# KSZ8851.net
KiCad netlist of a schematic drawn in EAGLE
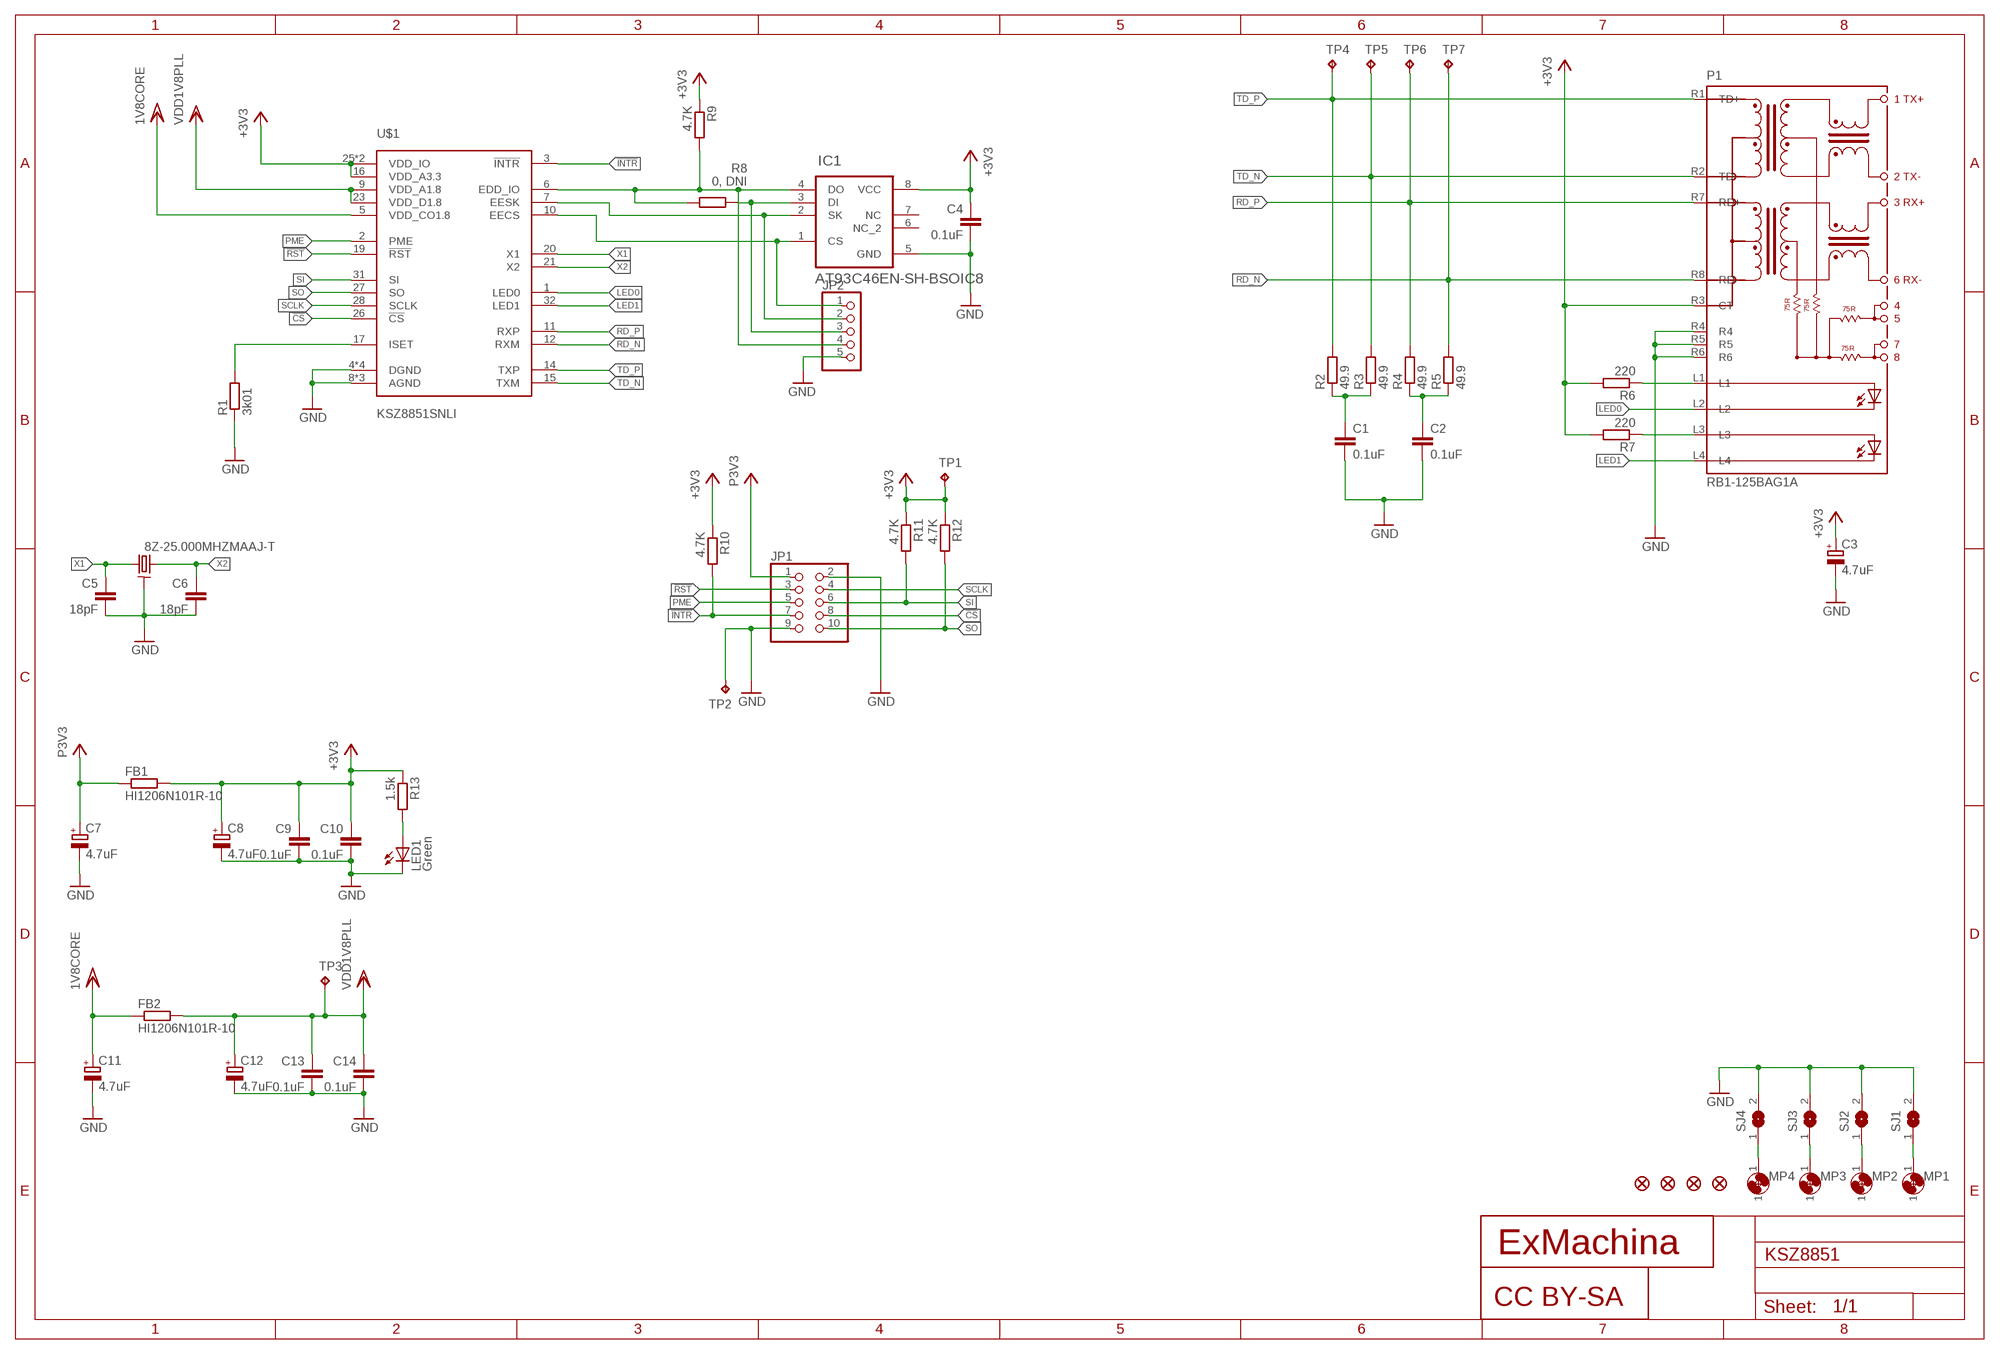
[diagram p0: schematic, sheet 1]

(export (version "E")
  (design (tool "Eeschema 10.0.6"))
  (components
    (comp (ref "-25.000MHZMAAJ-T1")
      (value "8Z-25.000MHZMAAJ-T")
      (footprint "eagle-import:SMD2.5X2")
      (fields (field (name "MPN") "8Z-25.000MAAJ-T"))
      (libsource (lib "eagle-import") (part "8Z-25.000MHZMAAJ-T"))
    )
    (comp (ref "C1")
      (value "0.1uF")
      (footprint "eagle-import:C0603")
      (fields (field (name "MPN") "MC0603B104K160CT"))
      (libsource (lib "eagle-import") (part "C-EUC0603"))
    )
    (comp (ref "C2")
      (value "0.1uF")
      (footprint "eagle-import:C0603")
      (fields (field (name "MPN") "MC0603B104K160CT"))
      (libsource (lib "eagle-import") (part "C-EUC0603"))
    )
    (comp (ref "C3")
      (value "4.7uF")
      (footprint "eagle-import:CT3216")
      (fields (field (name "MPN") "MCCTA475M010"))
      (libsource (lib "eagle-import") (part "CPOL-EUCT3216"))
    )
    (comp (ref "C4")
      (value "0.1uF")
      (footprint "eagle-import:C0603")
      (fields (field (name "MPN") "MC0603B104K160CT"))
      (libsource (lib "eagle-import") (part "C-EUC0603"))
    )
    (comp (ref "C5")
      (value "18pF")
      (footprint "eagle-import:C0603")
      (fields (field (name "MPN") "MC0603N180J500CT"))
      (libsource (lib "eagle-import") (part "C-EUC0603"))
    )
    (comp (ref "C6")
      (value "18pF")
      (footprint "eagle-import:C0603")
      (fields (field (name "MPN") "MC0603N180J500CT"))
      (libsource (lib "eagle-import") (part "C-EUC0603"))
    )
    (comp (ref "C7")
      (value "4.7uF")
      (footprint "eagle-import:CT3216")
      (fields (field (name "MPN") "MCCTA475M010"))
      (libsource (lib "eagle-import") (part "CPOL-EUCT3216"))
    )
    (comp (ref "C8")
      (value "4.7uF")
      (footprint "eagle-import:CT3216")
      (fields (field (name "MPN") "MCCTA475M010"))
      (libsource (lib "eagle-import") (part "CPOL-EUCT3216"))
    )
    (comp (ref "C9")
      (value "0.1uF")
      (footprint "eagle-import:C0603")
      (fields (field (name "MPN") "MC0603B104K160CT"))
      (libsource (lib "eagle-import") (part "C-EUC0603"))
    )
    (comp (ref "C10")
      (value "0.1uF")
      (footprint "eagle-import:C0603")
      (fields (field (name "MPN") "MC0603B104K160CT"))
      (libsource (lib "eagle-import") (part "C-EUC0603"))
    )
    (comp (ref "C11")
      (value "4.7uF")
      (footprint "eagle-import:CT3216")
      (fields (field (name "MPN") "MCCTA475M010"))
      (libsource (lib "eagle-import") (part "CPOL-EUCT3216"))
    )
    (comp (ref "C12")
      (value "4.7uF")
      (footprint "eagle-import:CT3216")
      (fields (field (name "MPN") "MCCTA475M010"))
      (libsource (lib "eagle-import") (part "CPOL-EUCT3216"))
    )
    (comp (ref "C13")
      (value "0.1uF")
      (footprint "eagle-import:C0603")
      (fields (field (name "MPN") "MC0603B104K160CT"))
      (libsource (lib "eagle-import") (part "C-EUC0603"))
    )
    (comp (ref "C14")
      (value "0.1uF")
      (footprint "eagle-import:C0603")
      (fields (field (name "MPN") "MC0603B104K160CT"))
      (libsource (lib "eagle-import") (part "C-EUC0603"))
    )
    (comp (ref "FB1")
      (value "HI1206N101R-10")
      (footprint "eagle-import:1206")
      (libsource (lib "eagle-import") (part "HI?N101R-101206"))
    )
    (comp (ref "FB2")
      (value "HI1206N101R-10")
      (footprint "eagle-import:1206")
      (libsource (lib "eagle-import") (part "HI?N101R-101206"))
    )
    (comp (ref "IC1")
      (value "AT93C46EN-SH-BSOIC8")
      (footprint "eagle-import:SOIC8")
      (fields (field (name "MPN") "AT93C46EN-SH-T"))
      (libsource (lib "eagle-import") (part "AT93C46EN-SH-BSOIC8"))
    )
    (comp (ref "JP1")
      (value "PINHD-2X5")
      (footprint "eagle-import:2X05")
      (fields (field (name "MPN") "M20-9980546"))
      (libsource (lib "eagle-import") (part "PINHD-2X5"))
    )
    (comp (ref "JP2")
      (value "PINHD-1X55X2MM")
      (footprint "eagle-import:1_05X2MM")
      (fields (field (name "MF") "FARNELL") (field (name "MPN") "M22-2010505"))
      (libsource (lib "eagle-import") (part "PINHD-1X55X2MM"))
    )
    (comp (ref "JP3")
      (value "FIDUCIAL1X2")
      (footprint "eagle-import:FIDUCIAL-1X2")
      (libsource (lib "eagle-import") (part "FIDUCIAL1X2"))
    )
    (comp (ref "JP4")
      (value "FIDUCIAL1X2")
      (footprint "eagle-import:FIDUCIAL-1X2")
      (libsource (lib "eagle-import") (part "FIDUCIAL1X2"))
    )
    (comp (ref "JP5")
      (value "FIDUCIAL1X2")
      (footprint "eagle-import:FIDUCIAL-1X2")
      (libsource (lib "eagle-import") (part "FIDUCIAL1X2"))
    )
    (comp (ref "JP6")
      (value "FIDUCIAL1X2")
      (footprint "eagle-import:FIDUCIAL-1X2")
      (libsource (lib "eagle-import") (part "FIDUCIAL1X2"))
    )
    (comp (ref "LED1")
      (value "Green")
      (footprint "eagle-import:SML0603")
      (fields (field (name "MPN") "OVS-0604"))
      (libsource (lib "eagle-import") (part "LEDSML0603"))
    )
    (comp (ref "MP1")
      (value "MOUNT-PAD2.5")
      (footprint "eagle-import:P2.5")
      (libsource (lib "eagle-import") (part "MOUNT-PAD2.5"))
    )
    (comp (ref "MP2")
      (value "MOUNT-PAD2.5")
      (footprint "eagle-import:P2.5")
      (libsource (lib "eagle-import") (part "MOUNT-PAD2.5"))
    )
    (comp (ref "MP3")
      (value "MOUNT-PAD2.5")
      (footprint "eagle-import:P2.5")
      (libsource (lib "eagle-import") (part "MOUNT-PAD2.5"))
    )
    (comp (ref "MP4")
      (value "MOUNT-PAD2.5")
      (footprint "eagle-import:P2.5")
      (libsource (lib "eagle-import") (part "MOUNT-PAD2.5"))
    )
    (comp (ref "P1")
      (value "RB1-125BAG1A")
      (footprint "eagle-import:WIZNET_RB1-125BAG1A")
      (libsource (lib "eagle-import") (part "RB1-125BAG1A"))
    )
    (comp (ref "R1")
      (value "3k01")
      (footprint "eagle-import:R0603")
      (fields (field (name "MPN") "MC0063W060313K01"))
      (libsource (lib "eagle-import") (part "R-EU_R0603"))
    )
    (comp (ref "R2")
      (value "49.9")
      (footprint "eagle-import:R0603")
      (fields (field (name "MPN") "MC0603SAF499JT5E"))
      (libsource (lib "eagle-import") (part "R-EU_R0603"))
    )
    (comp (ref "R3")
      (value "49.9")
      (footprint "eagle-import:R0603")
      (fields (field (name "MPN") "MC0603SAF499JT5E"))
      (libsource (lib "eagle-import") (part "R-EU_R0603"))
    )
    (comp (ref "R4")
      (value "49.9")
      (footprint "eagle-import:R0603")
      (fields (field (name "MPN") "MC0603SAF499JT5E"))
      (libsource (lib "eagle-import") (part "R-EU_R0603"))
    )
    (comp (ref "R5")
      (value "49.9")
      (footprint "eagle-import:R0603")
      (fields (field (name "MPN") "MC0603SAF499JT5E"))
      (libsource (lib "eagle-import") (part "R-EU_R0603"))
    )
    (comp (ref "R6")
      (value "220")
      (footprint "eagle-import:R0603")
      (fields (field (name "MF") "Multicomp Passives") (field (name "MPN") "MC0063W06031220R"))
      (libsource (lib "eagle-import") (part "R-EU_R0603"))
    )
    (comp (ref "R7")
      (value "220")
      (footprint "eagle-import:R0603")
      (fields (field (name "MF") "Multicomp Passives") (field (name "MPN") "MC0063W06031220R"))
      (libsource (lib "eagle-import") (part "R-EU_R0603"))
    )
    (comp (ref "R8")
      (value "0, DNI")
      (footprint "eagle-import:R0603")
      (fields (field (name "MF") "Multicomp Passives") (field (name "MPN") "MC0603WG00000T5E-TC"))
      (libsource (lib "eagle-import") (part "R-EU_R0603"))
    )
    (comp (ref "R9")
      (value "4.7K")
      (footprint "eagle-import:R0603")
      (fields (field (name "MF") "Multicomp Passives") (field (name "MPN") "MC0063W060314K7"))
      (libsource (lib "eagle-import") (part "R-EU_R0603"))
    )
    (comp (ref "R10")
      (value "4.7K")
      (footprint "eagle-import:R0603")
      (fields (field (name "MF") "Multicomp Passives") (field (name "MPN") "MC0063W060314K7"))
      (libsource (lib "eagle-import") (part "R-EU_R0603"))
    )
    (comp (ref "R11")
      (value "4.7K")
      (footprint "eagle-import:R0603")
      (fields (field (name "MF") "Multicomp Passives") (field (name "MPN") "MC0063W060314K7"))
      (libsource (lib "eagle-import") (part "R-EU_R0603"))
    )
    (comp (ref "R12")
      (value "4.7K")
      (footprint "eagle-import:R0603")
      (fields (field (name "MF") "Multicomp Passives") (field (name "MPN") "MC0063W060314K7"))
      (libsource (lib "eagle-import") (part "R-EU_R0603"))
    )
    (comp (ref "R13")
      (value "1.5k")
      (footprint "eagle-import:R0603")
      (fields (field (name "MPN") "MCMR06X1501FTL"))
      (libsource (lib "eagle-import") (part "R-EU_R0603"))
    )
    (comp (ref "SJ1") (value "SJ") (footprint "eagle-import:SJ") (libsource (lib "eagle-import") (part "SJ")))
    (comp (ref "SJ2") (value "SJ") (footprint "eagle-import:SJ") (libsource (lib "eagle-import") (part "SJ")))
    (comp (ref "SJ3") (value "SJ") (footprint "eagle-import:SJ") (libsource (lib "eagle-import") (part "SJ")))
    (comp (ref "SJ4") (value "SJ") (footprint "eagle-import:SJ") (libsource (lib "eagle-import") (part "SJ")))
    (comp (ref "TP1")
      (value "TPB2,54")
      (footprint "eagle-import:B2,54")
      (libsource (lib "eagle-import") (part "TPB2,54"))
    )
    (comp (ref "TP2")
      (value "TPB2,54")
      (footprint "eagle-import:B2,54")
      (libsource (lib "eagle-import") (part "TPB2,54"))
    )
    (comp (ref "TP3")
      (value "TPB2,54")
      (footprint "eagle-import:B2,54")
      (libsource (lib "eagle-import") (part "TPB2,54"))
    )
    (comp (ref "TP4")
      (value "TPB1,27")
      (footprint "eagle-import:B1,27")
      (libsource (lib "eagle-import") (part "TPB1,27"))
    )
    (comp (ref "TP5")
      (value "TPB1,27")
      (footprint "eagle-import:B1,27")
      (libsource (lib "eagle-import") (part "TPB1,27"))
    )
    (comp (ref "TP6")
      (value "TPB1,27")
      (footprint "eagle-import:B1,27")
      (libsource (lib "eagle-import") (part "TPB1,27"))
    )
    (comp (ref "TP7")
      (value "TPB1,27")
      (footprint "eagle-import:B1,27")
      (libsource (lib "eagle-import") (part "TPB1,27"))
    )
    (comp (ref "U$1")
      (value "KSZ8851SNLI")
      (footprint "eagle-import:QFN50P500X500X85-32L")
      (fields (field (name "MPN") "KSZ8851SNLI-TR"))
      (libsource (lib "eagle-import") (part "KSZ8851SNLI"))
    )
    (comp (ref "U$2")
      (value "EXMACHINA-LOGO-NAME")
      (footprint "eagle-import:EXM-LOGO-BASELINE")
      (libsource (lib "eagle-import") (part "EXMACHINA-LOGO-NAME"))
    )
    (comp (ref "U$3")
      (value "CC-BY-SA")
      (footprint "eagle-import:CC-BY-SA")
      (libsource (lib "eagle-import") (part "CC-BY-SA"))
    )
  )
  (nets
    (net (code "1") (name "+3V3") (class "Default")
      (node (ref "C10") (pin "1") (pinfunction "1_1") (pintype "passive"))
      (node (ref "C3") (pin "+") (pinfunction "+_+") (pintype "passive"))
      (node (ref "C4") (pin "1") (pinfunction "1_1") (pintype "passive"))
      (node (ref "C8") (pin "+") (pinfunction "+_+") (pintype "passive"))
      (node (ref "C9") (pin "1") (pinfunction "1_1") (pintype "passive"))
      (node (ref "FB1") (pin "2") (pinfunction "2_2") (pintype "passive"))
      (node (ref "IC1") (pin "8") (pinfunction "VCC_8") (pintype "power_in"))
      (node (ref "P1") (pin "R3") (pinfunction "CT_R3") (pintype "input"))
      (node (ref "R10") (pin "1") (pinfunction "1_1") (pintype "passive"))
      (node (ref "R11") (pin "1") (pinfunction "1_1") (pintype "passive"))
      (node (ref "R12") (pin "1") (pinfunction "1_1") (pintype "passive"))
      (node (ref "R13") (pin "1") (pinfunction "1_1") (pintype "passive"))
      (node (ref "R6") (pin "2") (pinfunction "2_2") (pintype "passive"))
      (node (ref "R7") (pin "2") (pinfunction "2_2") (pintype "passive"))
      (node (ref "R9") (pin "1") (pinfunction "1_1") (pintype "passive"))
      (node (ref "TP1") (pin "TP") (pinfunction "TP_TP") (pintype "input"))
      (node (ref "U$1") (pin "16") (pinfunction "VDD_A3.3_16") (pintype "power_in"))
      (node (ref "U$1") (pin "25") (pinfunction "VDD_IO_25") (pintype "power_in"))
      (node (ref "U$1") (pin "30") (pinfunction "VDD_IO_30") (pintype "power_in"))
    )
    (net (code "2") (name "/~{CS}") (class "Default")
      (node (ref "JP1") (pin "8") (pinfunction "8_8") (pintype "passive"))
      (node (ref "U$1") (pin "26") (pinfunction "~{CS}_26") (pintype "input"))
    )
    (net (code "3") (name "/~{INTR}") (class "Default")
      (node (ref "JP1") (pin "7") (pinfunction "7_7") (pintype "passive"))
      (node (ref "R10") (pin "2") (pinfunction "2_2") (pintype "passive"))
      (node (ref "U$1") (pin "3") (pinfunction "~{INTR}_3") (pintype "output"))
    )
    (net (code "4") (name "/~{RST}") (class "Default")
      (node (ref "JP1") (pin "3") (pinfunction "3_3") (pintype "passive"))
      (node (ref "U$1") (pin "19") (pinfunction "~{RST}_19") (pintype "input"))
    )
    (net (code "5") (name "1V8CORE") (class "Default")
      (node (ref "C11") (pin "+") (pinfunction "+_+") (pintype "passive"))
      (node (ref "FB2") (pin "1") (pinfunction "1_1") (pintype "passive"))
      (node (ref "U$1") (pin "5") (pinfunction "VDD_CO1.8_5") (pintype "power_in"))
    )
    (net (code "6") (name "GND") (class "Default")
      (node (ref "-25.000MHZMAAJ-T1") (pin "2") (pinfunction "2_2") (pintype "passive"))
      (node (ref "-25.000MHZMAAJ-T1") (pin "4") (pinfunction "2_4") (pintype "passive"))
      (node (ref "C1") (pin "2") (pinfunction "2_2") (pintype "passive"))
      (node (ref "C10") (pin "2") (pinfunction "2_2") (pintype "passive"))
      (node (ref "C11") (pin "-") (pinfunction "-_-") (pintype "passive"))
      (node (ref "C12") (pin "-") (pinfunction "-_-") (pintype "passive"))
      (node (ref "C13") (pin "2") (pinfunction "2_2") (pintype "passive"))
      (node (ref "C14") (pin "2") (pinfunction "2_2") (pintype "passive"))
      (node (ref "C2") (pin "2") (pinfunction "2_2") (pintype "passive"))
      (node (ref "C3") (pin "-") (pinfunction "-_-") (pintype "passive"))
      (node (ref "C4") (pin "2") (pinfunction "2_2") (pintype "passive"))
      (node (ref "C5") (pin "2") (pinfunction "2_2") (pintype "passive"))
      (node (ref "C6") (pin "2") (pinfunction "2_2") (pintype "passive"))
      (node (ref "C7") (pin "-") (pinfunction "-_-") (pintype "passive"))
      (node (ref "C8") (pin "-") (pinfunction "-_-") (pintype "passive"))
      (node (ref "C9") (pin "2") (pinfunction "2_2") (pintype "passive"))
      (node (ref "IC1") (pin "5") (pinfunction "GND_5") (pintype "passive"))
      (node (ref "JP1") (pin "2") (pinfunction "2_2") (pintype "passive"))
      (node (ref "JP1") (pin "9") (pinfunction "9_9") (pintype "passive"))
      (node (ref "JP2") (pin "5") (pinfunction "5_5") (pintype "passive"))
      (node (ref "LED1") (pin "C") (pinfunction "C_C") (pintype "passive"))
      (node (ref "P1") (pin "R4") (pinfunction "R4_R4") (pintype "input"))
      (node (ref "P1") (pin "R5") (pinfunction "R5_R5") (pintype "input"))
      (node (ref "P1") (pin "R6") (pinfunction "R6_R6") (pintype "input"))
      (node (ref "R1") (pin "1") (pinfunction "1_1") (pintype "passive"))
      (node (ref "SJ1") (pin "2") (pinfunction "2_2") (pintype "passive"))
      (node (ref "SJ2") (pin "2") (pinfunction "2_2") (pintype "passive"))
      (node (ref "SJ3") (pin "2") (pinfunction "2_2") (pintype "passive"))
      (node (ref "SJ4") (pin "2") (pinfunction "2_2") (pintype "passive"))
      (node (ref "TP2") (pin "TP") (pinfunction "TP_TP") (pintype "input"))
      (node (ref "U$1") (pin "13") (pinfunction "AGND_13") (pintype "power_in"))
      (node (ref "U$1") (pin "18") (pinfunction "AGND_18") (pintype "power_in"))
      (node (ref "U$1") (pin "22") (pinfunction "DGND_22") (pintype "power_in"))
      (node (ref "U$1") (pin "24") (pinfunction "DGND_24") (pintype "power_in"))
      (node (ref "U$1") (pin "29") (pinfunction "DGND_29") (pintype "power_in"))
      (node (ref "U$1") (pin "4") (pinfunction "DGND_4") (pintype "power_in"))
      (node (ref "U$1") (pin "8") (pinfunction "AGND_8") (pintype "power_in"))
    )
    (net (code "7") (name "LED0") (class "Default")
      (node (ref "P1") (pin "L2") (pinfunction "L2_L2") (pintype "passive"))
      (node (ref "U$1") (pin "1") (pinfunction "LED0_1") (pintype "bidirectional"))
    )
    (net (code "8") (name "LED1") (class "Default")
      (node (ref "P1") (pin "L4") (pinfunction "L4_L4") (pintype "passive"))
      (node (ref "U$1") (pin "32") (pinfunction "LED1_32") (pintype "bidirectional"))
    )
    (net (code "9") (name "MOUNT-PAD2.5") (class "Default")
      (node (ref "MP1") (pin "1") (pinfunction "1_1") (pintype "power_in"))
      (node (ref "MP2") (pin "1") (pinfunction "1_1") (pintype "power_in"))
      (node (ref "MP3") (pin "1") (pinfunction "1_1") (pintype "power_in"))
      (node (ref "MP4") (pin "1") (pinfunction "1_1") (pintype "power_in"))
      (node (ref "SJ1") (pin "1") (pinfunction "1_1") (pintype "passive"))
      (node (ref "SJ2") (pin "1") (pinfunction "1_1") (pintype "passive"))
      (node (ref "SJ3") (pin "1") (pinfunction "1_1") (pintype "passive"))
      (node (ref "SJ4") (pin "1") (pinfunction "1_1") (pintype "passive"))
    )
    (net (code "10") (name "Net-(C1-Pad1)") (class "Default")
      (node (ref "C1") (pin "1") (pinfunction "1_1") (pintype "passive"))
      (node (ref "R2") (pin "1") (pinfunction "1_1") (pintype "passive"))
      (node (ref "R3") (pin "1") (pinfunction "1_1") (pintype "passive"))
    )
    (net (code "11") (name "Net-(C2-Pad1)") (class "Default")
      (node (ref "C2") (pin "1") (pinfunction "1_1") (pintype "passive"))
      (node (ref "R4") (pin "1") (pinfunction "1_1") (pintype "passive"))
      (node (ref "R5") (pin "1") (pinfunction "1_1") (pintype "passive"))
    )
    (net (code "12") (name "Net-(IC1-CS)") (class "Default")
      (node (ref "IC1") (pin "1") (pinfunction "CS_1") (pintype "input"))
      (node (ref "JP2") (pin "1") (pinfunction "1_1") (pintype "passive"))
      (node (ref "U$1") (pin "10") (pinfunction "EECS_10") (pintype "output"))
    )
    (net (code "13") (name "Net-(IC1-DI)") (class "Default")
      (node (ref "IC1") (pin "3") (pinfunction "DI_3") (pintype "input"))
      (node (ref "JP2") (pin "3") (pinfunction "3_3") (pintype "passive"))
      (node (ref "R8") (pin "1") (pinfunction "1_1") (pintype "passive"))
    )
    (net (code "14") (name "Net-(IC1-DO)") (class "Default")
      (node (ref "IC1") (pin "4") (pinfunction "DO_4") (pintype "output"))
      (node (ref "JP2") (pin "4") (pinfunction "4_4") (pintype "passive"))
      (node (ref "R8") (pin "2") (pinfunction "2_2") (pintype "passive"))
      (node (ref "R9") (pin "2") (pinfunction "2_2") (pintype "passive"))
      (node (ref "U$1") (pin "6") (pinfunction "EDD_IO_6") (pintype "bidirectional"))
    )
    (net (code "15") (name "Net-(IC1-SK)") (class "Default")
      (node (ref "IC1") (pin "2") (pinfunction "SK_2") (pintype "input"))
      (node (ref "JP2") (pin "2") (pinfunction "2_2") (pintype "passive"))
      (node (ref "U$1") (pin "7") (pinfunction "EESK_7") (pintype "output"))
    )
    (net (code "16") (name "Net-(LED1-PadA)") (class "Default")
      (node (ref "LED1") (pin "A") (pinfunction "A_A") (pintype "passive"))
      (node (ref "R13") (pin "2") (pinfunction "2_2") (pintype "passive"))
    )
    (net (code "17") (name "Net-(P1-PadL1)") (class "Default")
      (node (ref "P1") (pin "L1") (pinfunction "L1_L1") (pintype "passive"))
      (node (ref "R6") (pin "1") (pinfunction "1_1") (pintype "passive"))
    )
    (net (code "18") (name "Net-(P1-PadL3)") (class "Default")
      (node (ref "P1") (pin "L3") (pinfunction "L3_L3") (pintype "passive"))
      (node (ref "R7") (pin "1") (pinfunction "1_1") (pintype "passive"))
    )
    (net (code "19") (name "Net-(U$1-ISET)") (class "Default")
      (node (ref "R1") (pin "2") (pinfunction "2_2") (pintype "passive"))
      (node (ref "U$1") (pin "17") (pinfunction "ISET_17") (pintype "output"))
    )
    (net (code "20") (name "P3V3") (class "Default")
      (node (ref "C7") (pin "+") (pinfunction "+_+") (pintype "passive"))
      (node (ref "FB1") (pin "1") (pinfunction "1_1") (pintype "passive"))
      (node (ref "JP1") (pin "1") (pinfunction "1_1") (pintype "passive"))
    )
    (net (code "21") (name "PME") (class "Default")
      (node (ref "JP1") (pin "5") (pinfunction "5_5") (pintype "passive"))
      (node (ref "U$1") (pin "2") (pinfunction "PME_2") (pintype "output"))
    )
    (net (code "22") (name "RD_N") (class "Default")
      (node (ref "P1") (pin "R8") (pinfunction "RD-_R8") (pintype "input"))
      (node (ref "R5") (pin "2") (pinfunction "2_2") (pintype "passive"))
      (node (ref "TP7") (pin "TP") (pinfunction "TP_TP") (pintype "input"))
      (node (ref "U$1") (pin "12") (pinfunction "RXM_12") (pintype "bidirectional"))
    )
    (net (code "23") (name "RD_P") (class "Default")
      (node (ref "P1") (pin "R7") (pinfunction "RD+_R7") (pintype "input"))
      (node (ref "R4") (pin "2") (pinfunction "2_2") (pintype "passive"))
      (node (ref "TP6") (pin "TP") (pinfunction "TP_TP") (pintype "input"))
      (node (ref "U$1") (pin "11") (pinfunction "RXP_11") (pintype "bidirectional"))
    )
    (net (code "24") (name "SCLK") (class "Default")
      (node (ref "JP1") (pin "4") (pinfunction "4_4") (pintype "passive"))
      (node (ref "U$1") (pin "28") (pinfunction "SCLK_28") (pintype "input"))
    )
    (net (code "25") (name "SI") (class "Default")
      (node (ref "JP1") (pin "6") (pinfunction "6_6") (pintype "passive"))
      (node (ref "R11") (pin "2") (pinfunction "2_2") (pintype "passive"))
      (node (ref "U$1") (pin "31") (pinfunction "SI_31") (pintype "input"))
    )
    (net (code "26") (name "SO") (class "Default")
      (node (ref "JP1") (pin "10") (pinfunction "10_10") (pintype "passive"))
      (node (ref "R12") (pin "2") (pinfunction "2_2") (pintype "passive"))
      (node (ref "U$1") (pin "27") (pinfunction "SO_27") (pintype "output"))
    )
    (net (code "27") (name "TD_N") (class "Default")
      (node (ref "P1") (pin "R2") (pinfunction "TD-_R2") (pintype "input"))
      (node (ref "R3") (pin "2") (pinfunction "2_2") (pintype "passive"))
      (node (ref "TP5") (pin "TP") (pinfunction "TP_TP") (pintype "input"))
      (node (ref "U$1") (pin "15") (pinfunction "TXM_15") (pintype "bidirectional"))
    )
    (net (code "28") (name "TD_P") (class "Default")
      (node (ref "P1") (pin "R1") (pinfunction "TD+_R1") (pintype "input"))
      (node (ref "R2") (pin "2") (pinfunction "2_2") (pintype "passive"))
      (node (ref "TP4") (pin "TP") (pinfunction "TP_TP") (pintype "input"))
      (node (ref "U$1") (pin "14") (pinfunction "TXP_14") (pintype "bidirectional"))
    )
    (net (code "29") (name "VDD1V8PLL") (class "Default")
      (node (ref "C12") (pin "+") (pinfunction "+_+") (pintype "passive"))
      (node (ref "C13") (pin "1") (pinfunction "1_1") (pintype "passive"))
      (node (ref "C14") (pin "1") (pinfunction "1_1") (pintype "passive"))
      (node (ref "FB2") (pin "2") (pinfunction "2_2") (pintype "passive"))
      (node (ref "TP3") (pin "TP") (pinfunction "TP_TP") (pintype "input"))
      (node (ref "U$1") (pin "23") (pinfunction "VDD_D1.8_23") (pintype "power_in"))
      (node (ref "U$1") (pin "9") (pinfunction "VDD_A1.8_9") (pintype "power_in"))
    )
    (net (code "30") (name "X1") (class "Default")
      (node (ref "-25.000MHZMAAJ-T1") (pin "1") (pinfunction "1_1") (pintype "passive"))
      (node (ref "C5") (pin "1") (pinfunction "1_1") (pintype "passive"))
      (node (ref "U$1") (pin "20") (pinfunction "X1_20") (pintype "output"))
    )
    (net (code "31") (name "X2") (class "Default")
      (node (ref "-25.000MHZMAAJ-T1") (pin "3") (pinfunction "3_3") (pintype "passive"))
      (node (ref "C6") (pin "1") (pinfunction "1_1") (pintype "passive"))
      (node (ref "U$1") (pin "21") (pinfunction "X2_21") (pintype "output"))
    )
    (net (code "32") (name "unconnected-(IC1-NC-Pad7)") (class "Default")
      (node (ref "IC1") (pin "7") (pinfunction "NC_7") (pintype "no_connect"))
    )
    (net (code "33") (name "unconnected-(IC1-NC_2-Pad6)") (class "Default")
      (node (ref "IC1") (pin "6") (pinfunction "NC_2_6") (pintype "no_connect"))
    )
  )
)
